# McPiFace-Status-V1.net
KiCad netlist of a schematic drawn in EAGLE
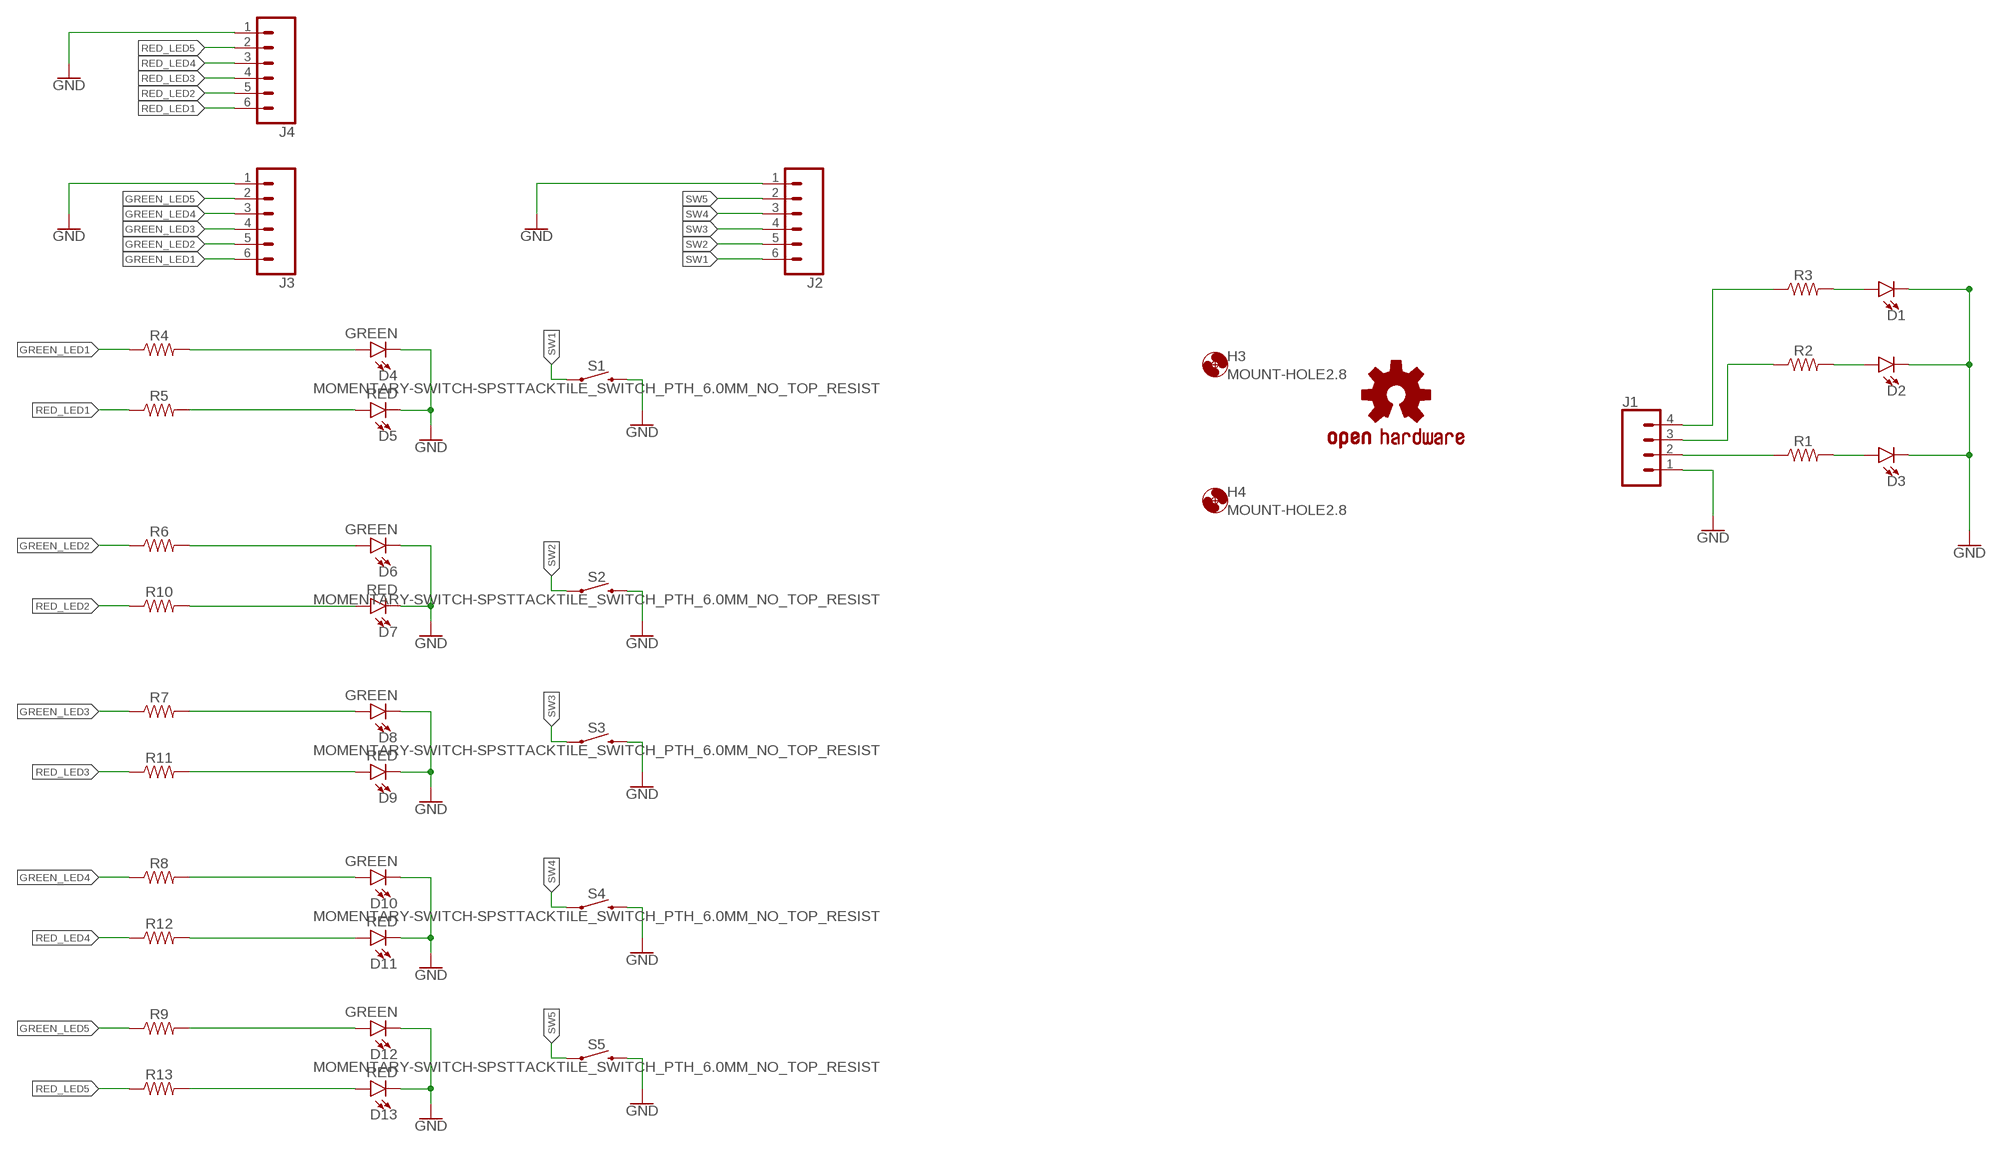
[diagram p0: schematic, sheet 1]

(export (version "E")
  (design (tool "Eeschema 10.0.6"))
  (components
    (comp (ref "D1")
      (value "LED1206-BOTTOM-1.6MM")
      (footprint "eagle-import:LED-1206-BOTTOM-1.6MM")
      (libsource (lib "eagle-import") (part "LED1206-BOTTOM-1.6MM"))
    )
    (comp (ref "D2")
      (value "LED1206-BOTTOM-1.6MM")
      (footprint "eagle-import:LED-1206-BOTTOM-1.6MM")
      (libsource (lib "eagle-import") (part "LED1206-BOTTOM-1.6MM"))
    )
    (comp (ref "D3")
      (value "LED1206-BOTTOM-1.6MM")
      (footprint "eagle-import:LED-1206-BOTTOM-1.6MM")
      (libsource (lib "eagle-import") (part "LED1206-BOTTOM-1.6MM"))
    )
    (comp (ref "D4")
      (value "GREEN")
      (footprint "eagle-import:LED-1206")
      (libsource (lib "eagle-import") (part "LED-GREEN1206"))
    )
    (comp (ref "D5")
      (value "RED")
      (footprint "eagle-import:LED-1206")
      (libsource (lib "eagle-import") (part "LED-RED1206"))
    )
    (comp (ref "D6")
      (value "GREEN")
      (footprint "eagle-import:LED-1206")
      (libsource (lib "eagle-import") (part "LED-GREEN1206"))
    )
    (comp (ref "D7")
      (value "RED")
      (footprint "eagle-import:LED-1206")
      (libsource (lib "eagle-import") (part "LED-RED1206"))
    )
    (comp (ref "D8")
      (value "GREEN")
      (footprint "eagle-import:LED-1206")
      (libsource (lib "eagle-import") (part "LED-GREEN1206"))
    )
    (comp (ref "D9")
      (value "RED")
      (footprint "eagle-import:LED-1206")
      (libsource (lib "eagle-import") (part "LED-RED1206"))
    )
    (comp (ref "D10")
      (value "GREEN")
      (footprint "eagle-import:LED-1206")
      (libsource (lib "eagle-import") (part "LED-GREEN1206"))
    )
    (comp (ref "D11")
      (value "RED")
      (footprint "eagle-import:LED-1206")
      (libsource (lib "eagle-import") (part "LED-RED1206"))
    )
    (comp (ref "D12")
      (value "GREEN")
      (footprint "eagle-import:LED-1206")
      (libsource (lib "eagle-import") (part "LED-GREEN1206"))
    )
    (comp (ref "D13")
      (value "RED")
      (footprint "eagle-import:LED-1206")
      (libsource (lib "eagle-import") (part "LED-RED1206"))
    )
    (comp (ref "H3")
      (value "MOUNT-HOLE2.8")
      (footprint "eagle-import:2,8")
      (libsource (lib "eagle-import") (part "MOUNT-HOLE2.8"))
    )
    (comp (ref "H4")
      (value "MOUNT-HOLE2.8")
      (footprint "eagle-import:2,8")
      (libsource (lib "eagle-import") (part "MOUNT-HOLE2.8"))
    )
    (comp (ref "J1")
      (value "CONN_04SMD2")
      (footprint "eagle-import:1X04_1MM_RA")
      (libsource (lib "eagle-import") (part "CONN_04SMD2"))
    )
    (comp (ref "J2")
      (value "CONN_06SMD-1MM")
      (footprint "eagle-import:1X06-1MM")
      (libsource (lib "eagle-import") (part "CONN_06SMD-1MM"))
    )
    (comp (ref "J3")
      (value "CONN_06SMD-1MM")
      (footprint "eagle-import:1X06-1MM")
      (libsource (lib "eagle-import") (part "CONN_06SMD-1MM"))
    )
    (comp (ref "J4")
      (value "CONN_06SMD-1MM")
      (footprint "eagle-import:1X06-1MM")
      (libsource (lib "eagle-import") (part "CONN_06SMD-1MM"))
    )
    (comp (ref "LOGO1")
      (value "OSHW-LOGOL")
      (footprint "eagle-import:OSHW-LOGO-L")
      (libsource (lib "eagle-import") (part "OSHW-LOGOL"))
    )
    (comp (ref "R1")
      (value "RESISTOR1206")
      (footprint "eagle-import:1206")
      (libsource (lib "eagle-import") (part "RESISTOR1206"))
    )
    (comp (ref "R2")
      (value "RESISTOR1206")
      (footprint "eagle-import:1206")
      (libsource (lib "eagle-import") (part "RESISTOR1206"))
    )
    (comp (ref "R3")
      (value "RESISTOR1206")
      (footprint "eagle-import:1206")
      (libsource (lib "eagle-import") (part "RESISTOR1206"))
    )
    (comp (ref "R4")
      (value "RESISTOR0805")
      (footprint "eagle-import:0805")
      (libsource (lib "eagle-import") (part "RESISTOR0805"))
    )
    (comp (ref "R5")
      (value "RESISTOR0805")
      (footprint "eagle-import:0805")
      (libsource (lib "eagle-import") (part "RESISTOR0805"))
    )
    (comp (ref "R6")
      (value "RESISTOR0805")
      (footprint "eagle-import:0805")
      (libsource (lib "eagle-import") (part "RESISTOR0805"))
    )
    (comp (ref "R7")
      (value "RESISTOR0805")
      (footprint "eagle-import:0805")
      (libsource (lib "eagle-import") (part "RESISTOR0805"))
    )
    (comp (ref "R8")
      (value "RESISTOR0805")
      (footprint "eagle-import:0805")
      (libsource (lib "eagle-import") (part "RESISTOR0805"))
    )
    (comp (ref "R9")
      (value "RESISTOR0805")
      (footprint "eagle-import:0805")
      (libsource (lib "eagle-import") (part "RESISTOR0805"))
    )
    (comp (ref "R10")
      (value "RESISTOR0805")
      (footprint "eagle-import:0805")
      (libsource (lib "eagle-import") (part "RESISTOR0805"))
    )
    (comp (ref "R11")
      (value "RESISTOR0805")
      (footprint "eagle-import:0805")
      (libsource (lib "eagle-import") (part "RESISTOR0805"))
    )
    (comp (ref "R12")
      (value "RESISTOR0805")
      (footprint "eagle-import:0805")
      (libsource (lib "eagle-import") (part "RESISTOR0805"))
    )
    (comp (ref "R13")
      (value "RESISTOR0805")
      (footprint "eagle-import:0805")
      (libsource (lib "eagle-import") (part "RESISTOR0805"))
    )
    (comp (ref "S1")
      (value "MOMENTARY-SWITCH-SPSTTACKTILE_SWITCH_PTH_6.0MM_NO_TOP_RESIST")
      (footprint "eagle-import:TACTILE_SWITCH_PTH_6.0MM_NO_TOP_RESIST")
      (libsource (lib "eagle-import") (part "MOMENTARY-SWITCH-SPSTTACKTILE_SWITCH_PTH_6.0MM_NO_TOP_RESIST"))
    )
    (comp (ref "S2")
      (value "MOMENTARY-SWITCH-SPSTTACKTILE_SWITCH_PTH_6.0MM_NO_TOP_RESIST")
      (footprint "eagle-import:TACTILE_SWITCH_PTH_6.0MM_NO_TOP_RESIST")
      (libsource (lib "eagle-import") (part "MOMENTARY-SWITCH-SPSTTACKTILE_SWITCH_PTH_6.0MM_NO_TOP_RESIST"))
    )
    (comp (ref "S3")
      (value "MOMENTARY-SWITCH-SPSTTACKTILE_SWITCH_PTH_6.0MM_NO_TOP_RESIST")
      (footprint "eagle-import:TACTILE_SWITCH_PTH_6.0MM_NO_TOP_RESIST")
      (libsource (lib "eagle-import") (part "MOMENTARY-SWITCH-SPSTTACKTILE_SWITCH_PTH_6.0MM_NO_TOP_RESIST"))
    )
    (comp (ref "S4")
      (value "MOMENTARY-SWITCH-SPSTTACKTILE_SWITCH_PTH_6.0MM_NO_TOP_RESIST")
      (footprint "eagle-import:TACTILE_SWITCH_PTH_6.0MM_NO_TOP_RESIST")
      (libsource (lib "eagle-import") (part "MOMENTARY-SWITCH-SPSTTACKTILE_SWITCH_PTH_6.0MM_NO_TOP_RESIST"))
    )
    (comp (ref "S5")
      (value "MOMENTARY-SWITCH-SPSTTACKTILE_SWITCH_PTH_6.0MM_NO_TOP_RESIST")
      (footprint "eagle-import:TACTILE_SWITCH_PTH_6.0MM_NO_TOP_RESIST")
      (libsource (lib "eagle-import") (part "MOMENTARY-SWITCH-SPSTTACKTILE_SWITCH_PTH_6.0MM_NO_TOP_RESIST"))
    )
  )
  (nets
    (net (code "1") (name "GND") (class "Default")
      (node (ref "D1") (pin "C") (pinfunction "C_C") (pintype "passive"))
      (node (ref "D10") (pin "C") (pinfunction "C_C") (pintype "passive"))
      (node (ref "D11") (pin "C") (pinfunction "C_C") (pintype "passive"))
      (node (ref "D12") (pin "C") (pinfunction "C_C") (pintype "passive"))
      (node (ref "D13") (pin "C") (pinfunction "C_C") (pintype "passive"))
      (node (ref "D2") (pin "C") (pinfunction "C_C") (pintype "passive"))
      (node (ref "D3") (pin "C") (pinfunction "C_C") (pintype "passive"))
      (node (ref "D4") (pin "C") (pinfunction "C_C") (pintype "passive"))
      (node (ref "D5") (pin "C") (pinfunction "C_C") (pintype "passive"))
      (node (ref "D6") (pin "C") (pinfunction "C_C") (pintype "passive"))
      (node (ref "D7") (pin "C") (pinfunction "C_C") (pintype "passive"))
      (node (ref "D8") (pin "C") (pinfunction "C_C") (pintype "passive"))
      (node (ref "D9") (pin "C") (pinfunction "C_C") (pintype "passive"))
      (node (ref "J1") (pin "1") (pinfunction "1_1") (pintype "passive"))
      (node (ref "J2") (pin "1") (pinfunction "1_1") (pintype "passive"))
      (node (ref "J3") (pin "1") (pinfunction "1_1") (pintype "passive"))
      (node (ref "J4") (pin "1") (pinfunction "1_1") (pintype "passive"))
      (node (ref "S1") (pin "3") (pinfunction "2_3") (pintype "passive"))
      (node (ref "S2") (pin "3") (pinfunction "2_3") (pintype "passive"))
      (node (ref "S3") (pin "3") (pinfunction "2_3") (pintype "passive"))
      (node (ref "S4") (pin "3") (pinfunction "2_3") (pintype "passive"))
      (node (ref "S5") (pin "3") (pinfunction "2_3") (pintype "passive"))
    )
    (net (code "2") (name "GREEN_LED1") (class "Default")
      (node (ref "J3") (pin "6") (pinfunction "6_6") (pintype "passive"))
      (node (ref "R4") (pin "1") (pinfunction "1_1") (pintype "passive"))
    )
    (net (code "3") (name "GREEN_LED2") (class "Default")
      (node (ref "J3") (pin "5") (pinfunction "5_5") (pintype "passive"))
      (node (ref "R6") (pin "1") (pinfunction "1_1") (pintype "passive"))
    )
    (net (code "4") (name "GREEN_LED3") (class "Default")
      (node (ref "J3") (pin "4") (pinfunction "4_4") (pintype "passive"))
      (node (ref "R7") (pin "1") (pinfunction "1_1") (pintype "passive"))
    )
    (net (code "5") (name "GREEN_LED4") (class "Default")
      (node (ref "J3") (pin "3") (pinfunction "3_3") (pintype "passive"))
      (node (ref "R8") (pin "1") (pinfunction "1_1") (pintype "passive"))
    )
    (net (code "6") (name "GREEN_LED5") (class "Default")
      (node (ref "J3") (pin "2") (pinfunction "2_2") (pintype "passive"))
      (node (ref "R9") (pin "1") (pinfunction "1_1") (pintype "passive"))
    )
    (net (code "7") (name "Net-(D1-PadA)") (class "Default")
      (node (ref "D1") (pin "A") (pinfunction "A_A") (pintype "passive"))
      (node (ref "R3") (pin "2") (pinfunction "2_2") (pintype "passive"))
    )
    (net (code "8") (name "Net-(D2-PadA)") (class "Default")
      (node (ref "D2") (pin "A") (pinfunction "A_A") (pintype "passive"))
      (node (ref "R2") (pin "2") (pinfunction "2_2") (pintype "passive"))
    )
    (net (code "9") (name "Net-(D3-PadA)") (class "Default")
      (node (ref "D3") (pin "A") (pinfunction "A_A") (pintype "passive"))
      (node (ref "R1") (pin "2") (pinfunction "2_2") (pintype "passive"))
    )
    (net (code "10") (name "Net-(D4-PadA)") (class "Default")
      (node (ref "D4") (pin "A") (pinfunction "A_A") (pintype "passive"))
      (node (ref "R4") (pin "2") (pinfunction "2_2") (pintype "passive"))
    )
    (net (code "11") (name "Net-(D5-PadA)") (class "Default")
      (node (ref "D5") (pin "A") (pinfunction "A_A") (pintype "passive"))
      (node (ref "R5") (pin "2") (pinfunction "2_2") (pintype "passive"))
    )
    (net (code "12") (name "Net-(D6-PadA)") (class "Default")
      (node (ref "D6") (pin "A") (pinfunction "A_A") (pintype "passive"))
      (node (ref "R6") (pin "2") (pinfunction "2_2") (pintype "passive"))
    )
    (net (code "13") (name "Net-(D7-PadA)") (class "Default")
      (node (ref "D7") (pin "A") (pinfunction "A_A") (pintype "passive"))
      (node (ref "R10") (pin "2") (pinfunction "2_2") (pintype "passive"))
    )
    (net (code "14") (name "Net-(D8-PadA)") (class "Default")
      (node (ref "D8") (pin "A") (pinfunction "A_A") (pintype "passive"))
      (node (ref "R7") (pin "2") (pinfunction "2_2") (pintype "passive"))
    )
    (net (code "15") (name "Net-(D9-PadA)") (class "Default")
      (node (ref "D9") (pin "A") (pinfunction "A_A") (pintype "passive"))
      (node (ref "R11") (pin "2") (pinfunction "2_2") (pintype "passive"))
    )
    (net (code "16") (name "Net-(D10-PadA)") (class "Default")
      (node (ref "D10") (pin "A") (pinfunction "A_A") (pintype "passive"))
      (node (ref "R8") (pin "2") (pinfunction "2_2") (pintype "passive"))
    )
    (net (code "17") (name "Net-(D11-PadA)") (class "Default")
      (node (ref "D11") (pin "A") (pinfunction "A_A") (pintype "passive"))
      (node (ref "R12") (pin "2") (pinfunction "2_2") (pintype "passive"))
    )
    (net (code "18") (name "Net-(D12-PadA)") (class "Default")
      (node (ref "D12") (pin "A") (pinfunction "A_A") (pintype "passive"))
      (node (ref "R9") (pin "2") (pinfunction "2_2") (pintype "passive"))
    )
    (net (code "19") (name "Net-(D13-PadA)") (class "Default")
      (node (ref "D13") (pin "A") (pinfunction "A_A") (pintype "passive"))
      (node (ref "R13") (pin "2") (pinfunction "2_2") (pintype "passive"))
    )
    (net (code "20") (name "Net-(J1-Pad2)") (class "Default")
      (node (ref "J1") (pin "2") (pinfunction "2_2") (pintype "passive"))
      (node (ref "R1") (pin "1") (pinfunction "1_1") (pintype "passive"))
    )
    (net (code "21") (name "Net-(J1-Pad3)") (class "Default")
      (node (ref "J1") (pin "3") (pinfunction "3_3") (pintype "passive"))
      (node (ref "R2") (pin "1") (pinfunction "1_1") (pintype "passive"))
    )
    (net (code "22") (name "Net-(J1-Pad4)") (class "Default")
      (node (ref "J1") (pin "4") (pinfunction "4_4") (pintype "passive"))
      (node (ref "R3") (pin "1") (pinfunction "1_1") (pintype "passive"))
    )
    (net (code "23") (name "RED_LED1") (class "Default")
      (node (ref "J4") (pin "6") (pinfunction "6_6") (pintype "passive"))
      (node (ref "R5") (pin "1") (pinfunction "1_1") (pintype "passive"))
    )
    (net (code "24") (name "RED_LED2") (class "Default")
      (node (ref "J4") (pin "5") (pinfunction "5_5") (pintype "passive"))
      (node (ref "R10") (pin "1") (pinfunction "1_1") (pintype "passive"))
    )
    (net (code "25") (name "RED_LED3") (class "Default")
      (node (ref "J4") (pin "4") (pinfunction "4_4") (pintype "passive"))
      (node (ref "R11") (pin "1") (pinfunction "1_1") (pintype "passive"))
    )
    (net (code "26") (name "RED_LED4") (class "Default")
      (node (ref "J4") (pin "3") (pinfunction "3_3") (pintype "passive"))
      (node (ref "R12") (pin "1") (pinfunction "1_1") (pintype "passive"))
    )
    (net (code "27") (name "RED_LED5") (class "Default")
      (node (ref "J4") (pin "2") (pinfunction "2_2") (pintype "passive"))
      (node (ref "R13") (pin "1") (pinfunction "1_1") (pintype "passive"))
    )
    (net (code "28") (name "SW1") (class "Default")
      (node (ref "J2") (pin "6") (pinfunction "6_6") (pintype "passive"))
      (node (ref "S1") (pin "1") (pinfunction "1_1") (pintype "passive"))
    )
    (net (code "29") (name "SW2") (class "Default")
      (node (ref "J2") (pin "5") (pinfunction "5_5") (pintype "passive"))
      (node (ref "S2") (pin "1") (pinfunction "1_1") (pintype "passive"))
    )
    (net (code "30") (name "SW3") (class "Default")
      (node (ref "J2") (pin "4") (pinfunction "4_4") (pintype "passive"))
      (node (ref "S3") (pin "1") (pinfunction "1_1") (pintype "passive"))
    )
    (net (code "31") (name "SW4") (class "Default")
      (node (ref "J2") (pin "3") (pinfunction "3_3") (pintype "passive"))
      (node (ref "S4") (pin "1") (pinfunction "1_1") (pintype "passive"))
    )
    (net (code "32") (name "SW5") (class "Default")
      (node (ref "J2") (pin "2") (pinfunction "2_2") (pintype "passive"))
      (node (ref "S5") (pin "1") (pinfunction "1_1") (pintype "passive"))
    )
  )
)
